# pcb1a.net
KiCad netlist of a schematic drawn in EAGLE
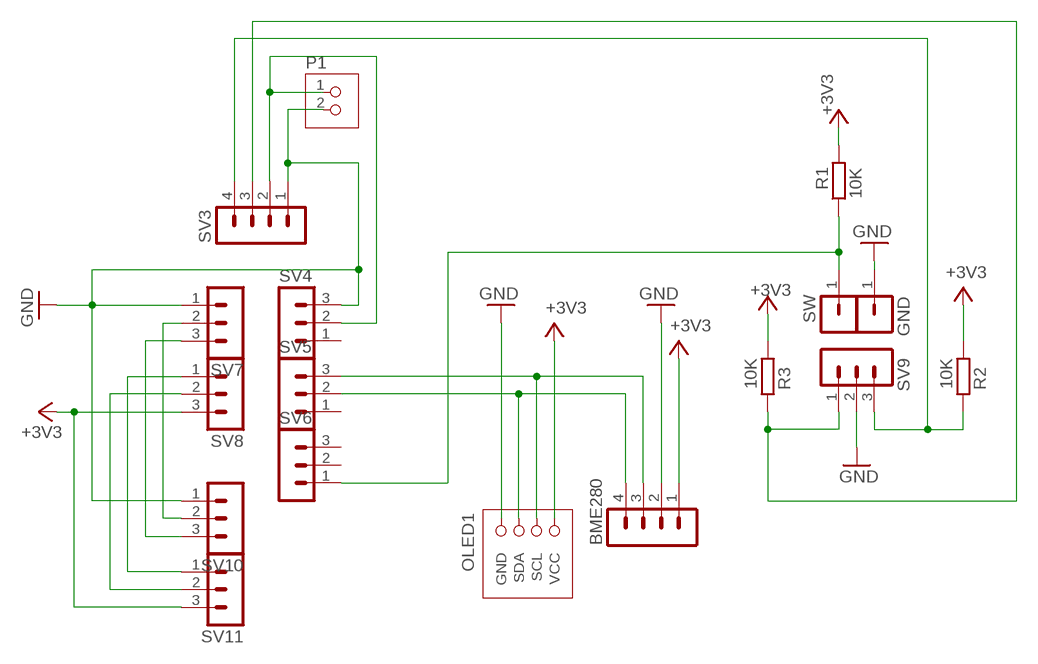
[diagram p0: schematic, sheet 1]

(export (version "E")
  (design (tool "Eeschema 10.0.6"))
  (components
    (comp (ref "BME280")
      (value "PINHEAD-MA04-1")
      (footprint "eagle-import:PINHEAD-MA04-1")
      (libsource (lib "eagle-import") (part "PINHEAD-MA04-1"))
    )
    (comp (ref "GND")
      (value "PINHEAD-MA01-1")
      (footprint "eagle-import:PINHEAD-MA01-1")
      (libsource (lib "eagle-import") (part "PINHEAD-MA01-1"))
    )
    (comp (ref "OLED1")
      (value "OLED-SSD1306-0.96")
      (footprint "eagle-import:OLED-I2C-0.96")
      (libsource (lib "eagle-import") (part "OLED-SSD1306-0.96"))
    )
    (comp (ref "P1")
      (value "JST-PH2")
      (footprint "eagle-import:JST-PH2")
      (libsource (lib "eagle-import") (part "JST-PH2"))
    )
    (comp (ref "R1")
      (value "10K")
      (footprint "eagle-import:0204_5")
      (libsource (lib "eagle-import") (part "R-EU_0204/5"))
    )
    (comp (ref "R2")
      (value "10K")
      (footprint "eagle-import:0204_5")
      (libsource (lib "eagle-import") (part "R-EU_0204/5"))
    )
    (comp (ref "R3")
      (value "10K")
      (footprint "eagle-import:0204_5")
      (libsource (lib "eagle-import") (part "R-EU_0204/5"))
    )
    (comp (ref "SV3")
      (value "PINHEAD-MA04-1")
      (footprint "eagle-import:PINHEAD-MA04-1")
      (libsource (lib "eagle-import") (part "PINHEAD-MA04-1"))
    )
    (comp (ref "SV4")
      (value "PINHEAD-MA03-1")
      (footprint "eagle-import:PINHEAD-MA03-1")
      (libsource (lib "eagle-import") (part "PINHEAD-MA03-1"))
    )
    (comp (ref "SV5")
      (value "PINHEAD-MA03-1")
      (footprint "eagle-import:PINHEAD-MA03-1")
      (libsource (lib "eagle-import") (part "PINHEAD-MA03-1"))
    )
    (comp (ref "SV6")
      (value "PINHEAD-MA03-1")
      (footprint "eagle-import:PINHEAD-MA03-1")
      (libsource (lib "eagle-import") (part "PINHEAD-MA03-1"))
    )
    (comp (ref "SV7")
      (value "PINHEAD-MA03-1")
      (footprint "eagle-import:PINHEAD-MA03-1")
      (libsource (lib "eagle-import") (part "PINHEAD-MA03-1"))
    )
    (comp (ref "SV8")
      (value "PINHEAD-MA03-1")
      (footprint "eagle-import:PINHEAD-MA03-1")
      (libsource (lib "eagle-import") (part "PINHEAD-MA03-1"))
    )
    (comp (ref "SV9")
      (value "PINHEAD-MA03-1")
      (footprint "eagle-import:PINHEAD-MA03-1")
      (libsource (lib "eagle-import") (part "PINHEAD-MA03-1"))
    )
    (comp (ref "SV10")
      (value "PINHEAD-MA03-1")
      (footprint "eagle-import:PINHEAD-MA03-1")
      (libsource (lib "eagle-import") (part "PINHEAD-MA03-1"))
    )
    (comp (ref "SV11")
      (value "PINHEAD-MA03-1")
      (footprint "eagle-import:PINHEAD-MA03-1")
      (libsource (lib "eagle-import") (part "PINHEAD-MA03-1"))
    )
    (comp (ref "SW")
      (value "PINHEAD-MA01-1")
      (footprint "eagle-import:PINHEAD-MA01-1")
      (libsource (lib "eagle-import") (part "PINHEAD-MA01-1"))
    )
  )
  (nets
    (net (code "1") (name "+3V3") (class "Default")
      (node (ref "BME280") (pin "1") (pinfunction "1_1") (pintype "passive"))
      (node (ref "OLED1") (pin "VCC") (pinfunction "VCC_VCC") (pintype "bidirectional"))
      (node (ref "R1") (pin "2") (pinfunction "2_2") (pintype "passive"))
      (node (ref "R2") (pin "1") (pinfunction "1_1") (pintype "passive"))
      (node (ref "R3") (pin "1") (pinfunction "1_1") (pintype "passive"))
      (node (ref "SV11") (pin "3") (pinfunction "3_3") (pintype "passive"))
      (node (ref "SV8") (pin "3") (pinfunction "3_3") (pintype "passive"))
    )
    (net (code "2") (name "GND") (class "Default")
      (node (ref "BME280") (pin "2") (pinfunction "2_2") (pintype "passive"))
      (node (ref "GND") (pin "1") (pinfunction "1_1") (pintype "passive"))
      (node (ref "OLED1") (pin "GND") (pinfunction "GND_GND") (pintype "bidirectional"))
      (node (ref "P1") (pin "2") (pinfunction "2_2") (pintype "passive"))
      (node (ref "SV10") (pin "1") (pinfunction "1_1") (pintype "passive"))
      (node (ref "SV3") (pin "1") (pinfunction "1_1") (pintype "passive"))
      (node (ref "SV4") (pin "3") (pinfunction "3_3") (pintype "passive"))
      (node (ref "SV7") (pin "1") (pinfunction "1_1") (pintype "passive"))
      (node (ref "SV9") (pin "2") (pinfunction "2_2") (pintype "passive"))
    )
    (net (code "3") (name "Net-(BME280-Pad3)") (class "Default")
      (node (ref "BME280") (pin "3") (pinfunction "3_3") (pintype "passive"))
      (node (ref "OLED1") (pin "SCL") (pinfunction "SCL_SCL") (pintype "bidirectional"))
      (node (ref "SV5") (pin "3") (pinfunction "3_3") (pintype "passive"))
    )
    (net (code "4") (name "Net-(BME280-Pad4)") (class "Default")
      (node (ref "BME280") (pin "4") (pinfunction "4_4") (pintype "passive"))
      (node (ref "OLED1") (pin "SDA") (pinfunction "SDA_SDA") (pintype "bidirectional"))
      (node (ref "SV5") (pin "2") (pinfunction "2_2") (pintype "passive"))
    )
    (net (code "5") (name "Net-(P1-Pad1)") (class "Default")
      (node (ref "P1") (pin "1") (pinfunction "1_1") (pintype "passive"))
      (node (ref "SV3") (pin "2") (pinfunction "2_2") (pintype "passive"))
      (node (ref "SV4") (pin "2") (pinfunction "2_2") (pintype "passive"))
    )
    (net (code "6") (name "Net-(R1-Pad1)") (class "Default")
      (node (ref "R1") (pin "1") (pinfunction "1_1") (pintype "passive"))
      (node (ref "SV6") (pin "1") (pinfunction "1_1") (pintype "passive"))
      (node (ref "SW") (pin "1") (pinfunction "1_1") (pintype "passive"))
    )
    (net (code "7") (name "Net-(R2-Pad2)") (class "Default")
      (node (ref "R2") (pin "2") (pinfunction "2_2") (pintype "passive"))
      (node (ref "SV3") (pin "4") (pinfunction "4_4") (pintype "passive"))
      (node (ref "SV9") (pin "3") (pinfunction "3_3") (pintype "passive"))
    )
    (net (code "8") (name "Net-(R3-Pad2)") (class "Default")
      (node (ref "R3") (pin "2") (pinfunction "2_2") (pintype "passive"))
      (node (ref "SV3") (pin "3") (pinfunction "3_3") (pintype "passive"))
      (node (ref "SV9") (pin "1") (pinfunction "1_1") (pintype "passive"))
    )
    (net (code "9") (name "Net-(SV10-Pad2)") (class "Default")
      (node (ref "SV10") (pin "2") (pinfunction "2_2") (pintype "passive"))
      (node (ref "SV7") (pin "2") (pinfunction "2_2") (pintype "passive"))
    )
    (net (code "10") (name "Net-(SV10-Pad3)") (class "Default")
      (node (ref "SV10") (pin "3") (pinfunction "3_3") (pintype "passive"))
      (node (ref "SV7") (pin "3") (pinfunction "3_3") (pintype "passive"))
    )
    (net (code "11") (name "Net-(SV11-Pad1)") (class "Default")
      (node (ref "SV11") (pin "1") (pinfunction "1_1") (pintype "passive"))
      (node (ref "SV8") (pin "1") (pinfunction "1_1") (pintype "passive"))
    )
    (net (code "12") (name "Net-(SV11-Pad2)") (class "Default")
      (node (ref "SV11") (pin "2") (pinfunction "2_2") (pintype "passive"))
      (node (ref "SV8") (pin "2") (pinfunction "2_2") (pintype "passive"))
    )
    (net (code "13") (name "unconnected-(SV4-Pad1)") (class "Default")
      (node (ref "SV4") (pin "1") (pinfunction "1_1") (pintype "passive"))
    )
    (net (code "14") (name "unconnected-(SV5-Pad1)") (class "Default")
      (node (ref "SV5") (pin "1") (pinfunction "1_1") (pintype "passive"))
    )
    (net (code "15") (name "unconnected-(SV6-Pad2)") (class "Default")
      (node (ref "SV6") (pin "2") (pinfunction "2_2") (pintype "passive"))
    )
    (net (code "16") (name "unconnected-(SV6-Pad3)") (class "Default")
      (node (ref "SV6") (pin "3") (pinfunction "3_3") (pintype "passive"))
    )
  )
)
